# VSCard.net
KiCad netlist of a schematic drawn in EAGLE
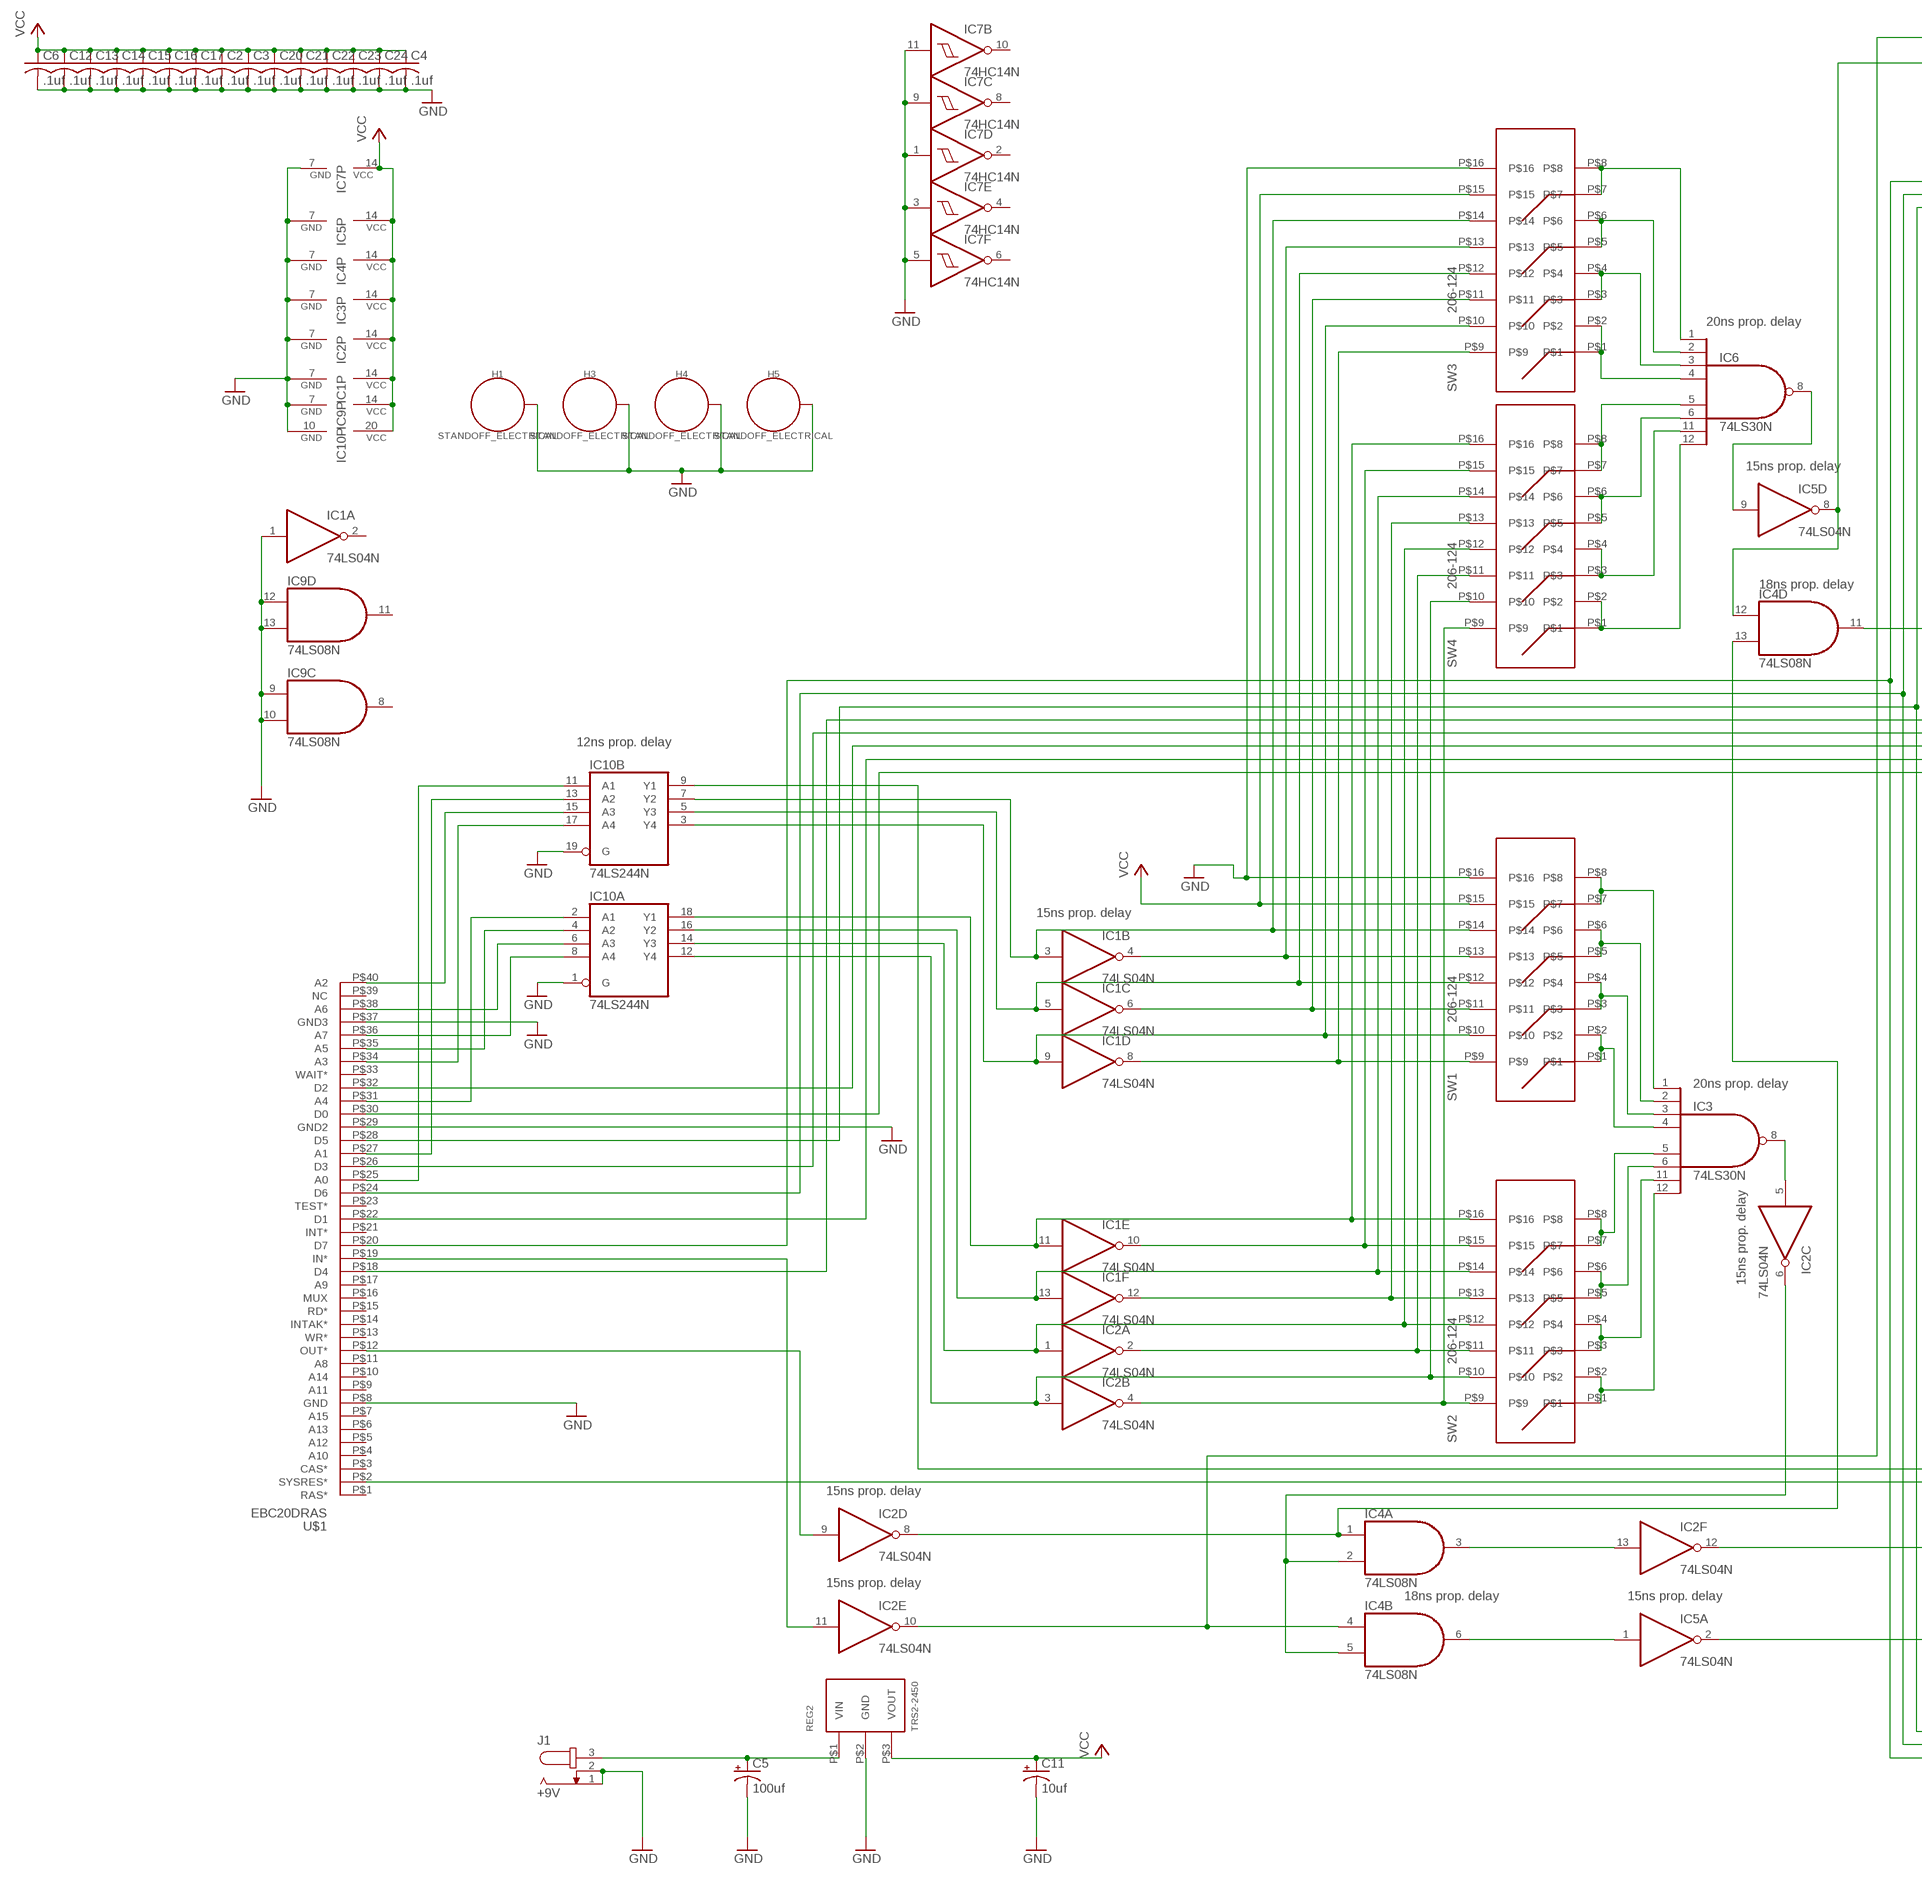
[diagram p0: schematic, sheet 1, part 1 of 3]
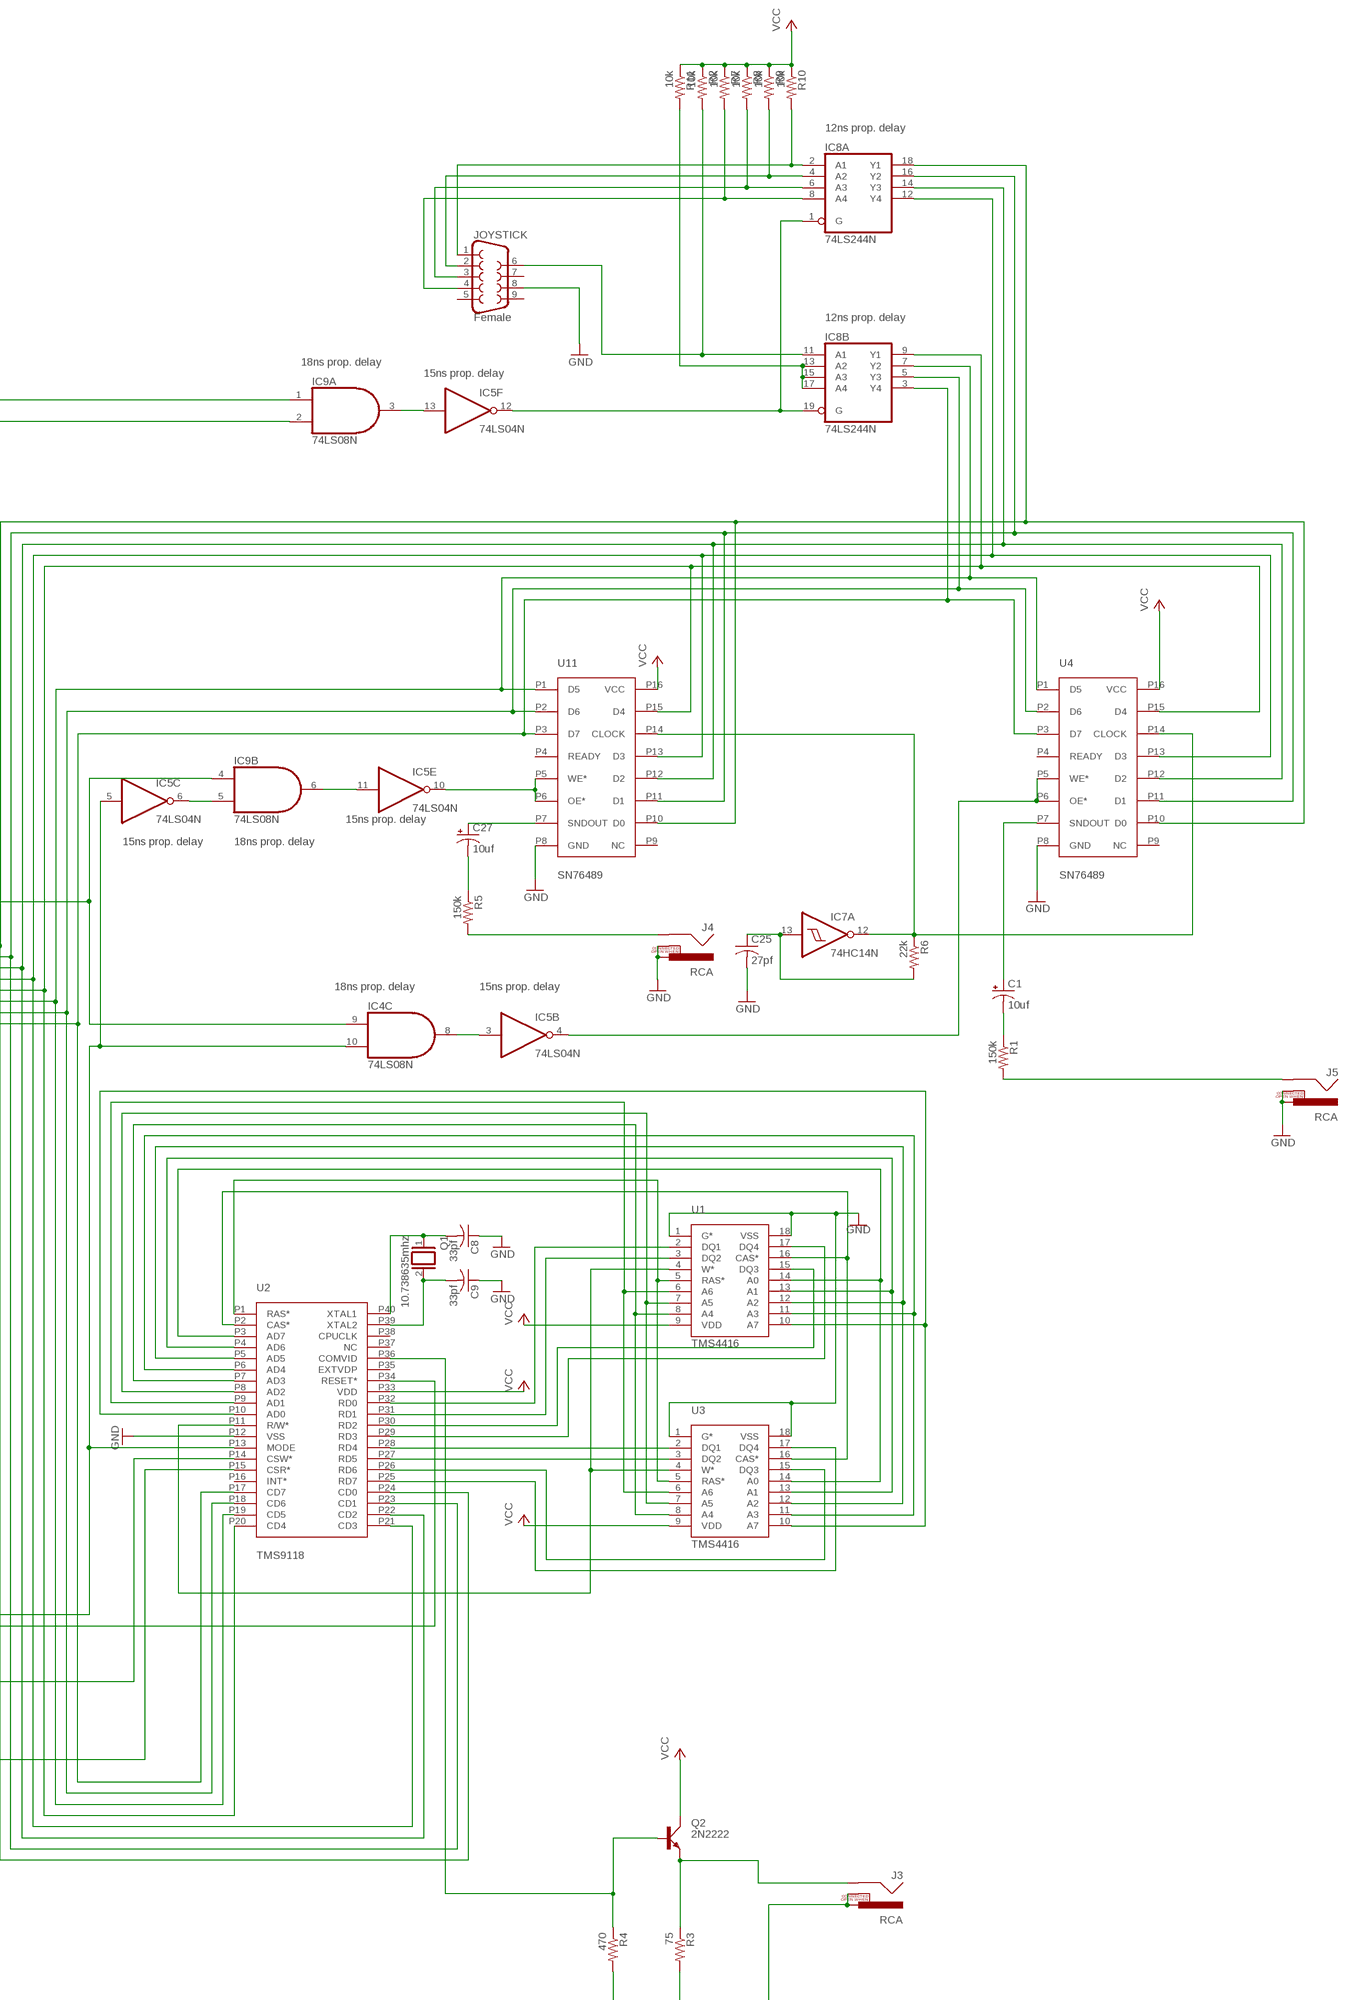
[diagram p1: schematic, sheet 1, part 2 of 3]
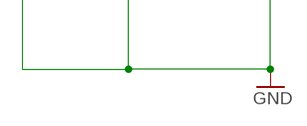
[diagram p2: schematic, sheet 1, part 3 of 3]

(export (version "E")
  (design (tool "Eeschema 10.0.6"))
  (components
    (comp (ref "C1")
      (value "10uf")
      (footprint "eagle-import:E2,5-6")
      (libsource (lib "eagle-import") (part "resistor_348_CPOL-USE2.5-6"))
    )
    (comp (ref "C2")
      (value ".1uf")
      (footprint "eagle-import:C025-025X050")
      (libsource (lib "eagle-import") (part "resistor_348_C-US025-025X050"))
    )
    (comp (ref "C3")
      (value ".1uf")
      (footprint "eagle-import:C025-025X050")
      (libsource (lib "eagle-import") (part "resistor_348_C-US025-025X050"))
    )
    (comp (ref "C4")
      (value ".1uf")
      (footprint "eagle-import:C025-025X050")
      (libsource (lib "eagle-import") (part "resistor_348_C-US025-025X050"))
    )
    (comp (ref "C5")
      (value "100uf")
      (footprint "eagle-import:E3,5-10")
      (libsource (lib "eagle-import") (part "CPOL-USE3.5-10"))
    )
    (comp (ref "C6")
      (value ".1uf")
      (footprint "eagle-import:C025-025X050")
      (libsource (lib "eagle-import") (part "resistor_348_C-US025-025X050"))
    )
    (comp (ref "C8")
      (value "33pf")
      (footprint "eagle-import:C050-050X075")
      (libsource (lib "eagle-import") (part "C-US050-050X075"))
    )
    (comp (ref "C9")
      (value "33pf")
      (footprint "eagle-import:C050-050X075")
      (libsource (lib "eagle-import") (part "C-US050-050X075"))
    )
    (comp (ref "C11")
      (value "10uf")
      (footprint "eagle-import:E3,5-10")
      (libsource (lib "eagle-import") (part "CPOL-USE3.5-10"))
    )
    (comp (ref "C12")
      (value ".1uf")
      (footprint "eagle-import:C025-025X050")
      (libsource (lib "eagle-import") (part "resistor_348_C-US025-025X050"))
    )
    (comp (ref "C13")
      (value ".1uf")
      (footprint "eagle-import:C025-025X050")
      (libsource (lib "eagle-import") (part "resistor_348_C-US025-025X050"))
    )
    (comp (ref "C14")
      (value ".1uf")
      (footprint "eagle-import:C025-025X050")
      (libsource (lib "eagle-import") (part "resistor_348_C-US025-025X050"))
    )
    (comp (ref "C15")
      (value ".1uf")
      (footprint "eagle-import:C025-025X050")
      (libsource (lib "eagle-import") (part "resistor_348_C-US025-025X050"))
    )
    (comp (ref "C16")
      (value ".1uf")
      (footprint "eagle-import:C025-025X050")
      (libsource (lib "eagle-import") (part "resistor_348_C-US025-025X050"))
    )
    (comp (ref "C17")
      (value ".1uf")
      (footprint "eagle-import:C025-025X050")
      (libsource (lib "eagle-import") (part "resistor_348_C-US025-025X050"))
    )
    (comp (ref "C20")
      (value ".1uf")
      (footprint "eagle-import:C025-025X050")
      (libsource (lib "eagle-import") (part "resistor_348_C-US025-025X050"))
    )
    (comp (ref "C21")
      (value ".1uf")
      (footprint "eagle-import:C025-025X050")
      (libsource (lib "eagle-import") (part "resistor_348_C-US025-025X050"))
    )
    (comp (ref "C22")
      (value ".1uf")
      (footprint "eagle-import:C025-025X050")
      (libsource (lib "eagle-import") (part "resistor_348_C-US025-025X050"))
    )
    (comp (ref "C23")
      (value ".1uf")
      (footprint "eagle-import:C025-025X050")
      (libsource (lib "eagle-import") (part "resistor_348_C-US025-025X050"))
    )
    (comp (ref "C24")
      (value ".1uf")
      (footprint "eagle-import:C025-025X050")
      (libsource (lib "eagle-import") (part "resistor_348_C-US025-025X050"))
    )
    (comp (ref "C25")
      (value "27pf")
      (footprint "eagle-import:C025-025X050")
      (libsource (lib "eagle-import") (part "resistor_348_C-US025-025X050"))
    )
    (comp (ref "C27")
      (value "10uf")
      (footprint "eagle-import:E2,5-6")
      (libsource (lib "eagle-import") (part "resistor_348_CPOL-USE2.5-6"))
    )
    (comp (ref "H1")
      (value "STANDOFF_ELECTRICAL")
      (footprint "eagle-import:STANDOFF-ELECTRICAL")
      (libsource (lib "eagle-import") (part "STANDOFF_ELECTRICAL"))
    )
    (comp (ref "H3")
      (value "STANDOFF_ELECTRICAL")
      (footprint "eagle-import:STANDOFF-ELECTRICAL")
      (libsource (lib "eagle-import") (part "STANDOFF_ELECTRICAL"))
    )
    (comp (ref "H4")
      (value "STANDOFF_ELECTRICAL")
      (footprint "eagle-import:STANDOFF-ELECTRICAL")
      (libsource (lib "eagle-import") (part "STANDOFF_ELECTRICAL"))
    )
    (comp (ref "H5")
      (value "STANDOFF_ELECTRICAL")
      (footprint "eagle-import:STANDOFF-ELECTRICAL")
      (libsource (lib "eagle-import") (part "STANDOFF_ELECTRICAL"))
    )
    (comp (ref "IC1")
      (value "74LS04N")
      (footprint "eagle-import:DIL14")
      (libsource (lib "eagle-import") (part "7404NLS"))
    )
    (comp (ref "IC2")
      (value "74LS04N")
      (footprint "eagle-import:DIL14")
      (libsource (lib "eagle-import") (part "7404NLS"))
    )
    (comp (ref "IC3")
      (value "74LS30N")
      (footprint "eagle-import:DIL14")
      (libsource (lib "eagle-import") (part "7430NLS"))
    )
    (comp (ref "IC4")
      (value "74LS08N")
      (footprint "eagle-import:DIL14")
      (libsource (lib "eagle-import") (part "7408NLS"))
    )
    (comp (ref "IC5")
      (value "74LS04N")
      (footprint "eagle-import:DIL14")
      (libsource (lib "eagle-import") (part "7404NLS"))
    )
    (comp (ref "IC6")
      (value "74LS30N")
      (footprint "eagle-import:DIL14")
      (libsource (lib "eagle-import") (part "7430NLS"))
    )
    (comp (ref "IC7")
      (value "74HC14N")
      (footprint "eagle-import:DIL14")
      (libsource (lib "eagle-import") (part "7414NHC"))
    )
    (comp (ref "IC8")
      (value "74LS244N")
      (footprint "eagle-import:DIL20")
      (libsource (lib "eagle-import") (part "74244NLS"))
    )
    (comp (ref "IC9")
      (value "74LS08N")
      (footprint "eagle-import:DIL14")
      (libsource (lib "eagle-import") (part "7408NLS"))
    )
    (comp (ref "IC10")
      (value "74LS244N")
      (footprint "eagle-import:DIL20")
      (libsource (lib "eagle-import") (part "74244NLS"))
    )
    (comp (ref "J1")
      (value "+9V")
      (footprint "eagle-import:SPC4077")
      (libsource (lib "eagle-import") (part "JACK-PLUG0"))
    )
    (comp (ref "J3")
      (value "RCA")
      (footprint "eagle-import:RCA")
      (libsource (lib "eagle-import") (part "RCA"))
    )
    (comp (ref "J4")
      (value "RCA")
      (footprint "eagle-import:RCA")
      (libsource (lib "eagle-import") (part "RCA"))
    )
    (comp (ref "J5")
      (value "RCA")
      (footprint "eagle-import:RCA")
      (libsource (lib "eagle-import") (part "RCA"))
    )
    (comp (ref "JOYSTICK")
      (value "Female")
      (footprint "eagle-import:DB9")
      (libsource (lib "eagle-import") (part "DB9FEMALE"))
    )
    (comp (ref "Q1")
      (value "10.738635mhz")
      (footprint "eagle-import:QS")
      (libsource (lib "eagle-import") (part "XTAL/S"))
    )
    (comp (ref "Q2")
      (value "2N2222")
      (footprint "eagle-import:TO18A")
      (libsource (lib "eagle-import") (part "2N2222"))
    )
    (comp (ref "R1")
      (value "150k")
      (footprint "eagle-import:0207_2V")
      (libsource (lib "eagle-import") (part "R-US_0207/2V"))
    )
    (comp (ref "R2")
      (value "10k")
      (footprint "eagle-import:0207_2V")
      (libsource (lib "eagle-import") (part "R-US_0207/2V"))
    )
    (comp (ref "R3")
      (value "75")
      (footprint "eagle-import:0207_2V")
      (libsource (lib "eagle-import") (part "R-US_0207/2V"))
    )
    (comp (ref "R4")
      (value "470")
      (footprint "eagle-import:0207_2V")
      (libsource (lib "eagle-import") (part "R-US_0207/2V"))
    )
    (comp (ref "R5")
      (value "150k")
      (footprint "eagle-import:0207_2V")
      (libsource (lib "eagle-import") (part "R-US_0207/2V"))
    )
    (comp (ref "R6")
      (value "22k")
      (footprint "eagle-import:0207_2V")
      (libsource (lib "eagle-import") (part "R-US_0207/2V"))
    )
    (comp (ref "R7")
      (value "10k")
      (footprint "eagle-import:0207_2V")
      (libsource (lib "eagle-import") (part "R-US_0207/2V"))
    )
    (comp (ref "R8")
      (value "10k")
      (footprint "eagle-import:0207_2V")
      (libsource (lib "eagle-import") (part "R-US_0207/2V"))
    )
    (comp (ref "R9")
      (value "10k")
      (footprint "eagle-import:0207_2V")
      (libsource (lib "eagle-import") (part "R-US_0207/2V"))
    )
    (comp (ref "R10")
      (value "10k")
      (footprint "eagle-import:0207_2V")
      (libsource (lib "eagle-import") (part "R-US_0207/2V"))
    )
    (comp (ref "R11")
      (value "10k")
      (footprint "eagle-import:0207_2V")
      (libsource (lib "eagle-import") (part "R-US_0207/2V"))
    )
    (comp (ref "REG2")
      (value "TRS2-2450")
      (footprint "eagle-import:TRACON_REG")
      (libsource (lib "eagle-import") (part "TRS2-2450"))
    )
    (comp (ref "SW1")
      (value "206-124")
      (footprint "eagle-import:206-124")
      (libsource (lib "eagle-import") (part "206-124"))
    )
    (comp (ref "SW2")
      (value "206-124")
      (footprint "eagle-import:206-124")
      (libsource (lib "eagle-import") (part "206-124"))
    )
    (comp (ref "SW3")
      (value "206-124")
      (footprint "eagle-import:206-124")
      (libsource (lib "eagle-import") (part "206-124"))
    )
    (comp (ref "SW4")
      (value "206-124")
      (footprint "eagle-import:206-124")
      (libsource (lib "eagle-import") (part "206-124"))
    )
    (comp (ref "U$1")
      (value "EBC20DRAS")
      (footprint "eagle-import:EBC20DRAS")
      (libsource (lib "eagle-import") (part "EBC20DRAS"))
    )
    (comp (ref "U1")
      (value "TMS4416")
      (footprint "eagle-import:DIP18")
      (libsource (lib "eagle-import") (part "TMS4416"))
    )
    (comp (ref "U2")
      (value "TMS9118")
      (footprint "eagle-import:DIP40_MCU")
      (libsource (lib "eagle-import") (part "TMS9118"))
    )
    (comp (ref "U3")
      (value "TMS4416")
      (footprint "eagle-import:DIP18")
      (libsource (lib "eagle-import") (part "TMS4416"))
    )
    (comp (ref "U4")
      (value "SN76489")
      (footprint "eagle-import:DIP16")
      (libsource (lib "eagle-import") (part "SN76489"))
    )
    (comp (ref "U11")
      (value "SN76489")
      (footprint "eagle-import:DIP16")
      (libsource (lib "eagle-import") (part "SN76489"))
    )
  )
  (nets
    (net (code "1") (name "GND") (class "Default")
      (node (ref "C11") (pin "-") (pinfunction "-_-") (pintype "passive"))
      (node (ref "C12") (pin "2") (pinfunction "2_2") (pintype "passive"))
      (node (ref "C13") (pin "2") (pinfunction "2_2") (pintype "passive"))
      (node (ref "C14") (pin "2") (pinfunction "2_2") (pintype "passive"))
      (node (ref "C15") (pin "2") (pinfunction "2_2") (pintype "passive"))
      (node (ref "C16") (pin "2") (pinfunction "2_2") (pintype "passive"))
      (node (ref "C17") (pin "2") (pinfunction "2_2") (pintype "passive"))
      (node (ref "C2") (pin "2") (pinfunction "2_2") (pintype "passive"))
      (node (ref "C20") (pin "2") (pinfunction "2_2") (pintype "passive"))
      (node (ref "C21") (pin "2") (pinfunction "2_2") (pintype "passive"))
      (node (ref "C22") (pin "2") (pinfunction "2_2") (pintype "passive"))
      (node (ref "C23") (pin "2") (pinfunction "2_2") (pintype "passive"))
      (node (ref "C24") (pin "2") (pinfunction "2_2") (pintype "passive"))
      (node (ref "C25") (pin "2") (pinfunction "2_2") (pintype "passive"))
      (node (ref "C3") (pin "2") (pinfunction "2_2") (pintype "passive"))
      (node (ref "C4") (pin "2") (pinfunction "2_2") (pintype "passive"))
      (node (ref "C5") (pin "-") (pinfunction "-_-") (pintype "passive"))
      (node (ref "C6") (pin "2") (pinfunction "2_2") (pintype "passive"))
      (node (ref "C8") (pin "1") (pinfunction "1_1") (pintype "passive"))
      (node (ref "C9") (pin "1") (pinfunction "1_1") (pintype "passive"))
      (node (ref "H1") (pin "P1") (pinfunction "P$1_P1") (pintype "bidirectional"))
      (node (ref "H3") (pin "P1") (pinfunction "P$1_P1") (pintype "bidirectional"))
      (node (ref "H4") (pin "P1") (pinfunction "P$1_P1") (pintype "bidirectional"))
      (node (ref "H5") (pin "P1") (pinfunction "P$1_P1") (pintype "bidirectional"))
      (node (ref "IC1") (pin "1") (pinfunction "I_1") (pintype "input"))
      (node (ref "IC1") (pin "7") (pinfunction "GND_7") (pintype "power_in"))
      (node (ref "IC10") (pin "1") (pinfunction "G_1") (pintype "input"))
      (node (ref "IC10") (pin "10") (pinfunction "GND_10") (pintype "power_in"))
      (node (ref "IC10") (pin "19") (pinfunction "G_19") (pintype "input"))
      (node (ref "IC2") (pin "7") (pinfunction "GND_7") (pintype "power_in"))
      (node (ref "IC3") (pin "7") (pinfunction "GND_7") (pintype "power_in"))
      (node (ref "IC4") (pin "7") (pinfunction "GND_7") (pintype "power_in"))
      (node (ref "IC5") (pin "7") (pinfunction "GND_7") (pintype "power_in"))
      (node (ref "IC7") (pin "1") (pinfunction "I_1") (pintype "input"))
      (node (ref "IC7") (pin "11") (pinfunction "I_11") (pintype "input"))
      (node (ref "IC7") (pin "3") (pinfunction "I_3") (pintype "input"))
      (node (ref "IC7") (pin "5") (pinfunction "I_5") (pintype "input"))
      (node (ref "IC7") (pin "7") (pinfunction "GND_7") (pintype "power_in"))
      (node (ref "IC7") (pin "9") (pinfunction "I_9") (pintype "input"))
      (node (ref "IC9") (pin "10") (pinfunction "I1_10") (pintype "input"))
      (node (ref "IC9") (pin "12") (pinfunction "I0_12") (pintype "input"))
      (node (ref "IC9") (pin "13") (pinfunction "I1_13") (pintype "input"))
      (node (ref "IC9") (pin "7") (pinfunction "GND_7") (pintype "power_in"))
      (node (ref "IC9") (pin "9") (pinfunction "I0_9") (pintype "input"))
      (node (ref "J1") (pin "1") (pinfunction "1_1") (pintype "passive"))
      (node (ref "J1") (pin "2") (pinfunction "2_2") (pintype "passive"))
      (node (ref "J3") (pin "PIN") (pinfunction "PIN_PIN") (pintype "bidirectional"))
      (node (ref "J3") (pin "SWITCH") (pinfunction "SWITCH_SWITCH") (pintype "bidirectional"))
      (node (ref "J4") (pin "PIN") (pinfunction "PIN_PIN") (pintype "bidirectional"))
      (node (ref "J4") (pin "SWITCH") (pinfunction "SWITCH_SWITCH") (pintype "bidirectional"))
      (node (ref "J5") (pin "PIN") (pinfunction "PIN_PIN") (pintype "bidirectional"))
      (node (ref "J5") (pin "SWITCH") (pinfunction "SWITCH_SWITCH") (pintype "bidirectional"))
      (node (ref "JOYSTICK") (pin "8") (pinfunction "8_8") (pintype "passive"))
      (node (ref "R3") (pin "2") (pinfunction "2_2") (pintype "passive"))
      (node (ref "R4") (pin "2") (pinfunction "2_2") (pintype "passive"))
      (node (ref "REG2") (pin "P$2") (pinfunction "GND_P$2") (pintype "bidirectional"))
      (node (ref "SW1") (pin "P$16") (pinfunction "P$16_P$16") (pintype "bidirectional"))
      (node (ref "SW3") (pin "P$16") (pinfunction "P$16_P$16") (pintype "bidirectional"))
      (node (ref "U$1") (pin "P$29") (pinfunction "GND2_P$29") (pintype "bidirectional"))
      (node (ref "U$1") (pin "P$37") (pinfunction "GND3_P$37") (pintype "bidirectional"))
      (node (ref "U$1") (pin "P$8") (pinfunction "GND_P$8") (pintype "bidirectional"))
      (node (ref "U1") (pin "1") (pinfunction "G*_1") (pintype "bidirectional"))
      (node (ref "U1") (pin "18") (pinfunction "VSS_18") (pintype "bidirectional"))
      (node (ref "U11") (pin "P8") (pinfunction "GND_P8") (pintype "bidirectional"))
      (node (ref "U2") (pin "P12") (pinfunction "VSS_P12") (pintype "bidirectional"))
      (node (ref "U3") (pin "1") (pinfunction "G*_1") (pintype "bidirectional"))
      (node (ref "U3") (pin "18") (pinfunction "VSS_18") (pintype "bidirectional"))
      (node (ref "U4") (pin "P8") (pinfunction "GND_P8") (pintype "bidirectional"))
    )
    (net (code "2") (name "Net-(C1-Pad-)") (class "Default")
      (node (ref "C1") (pin "-") (pinfunction "-_-") (pintype "passive"))
      (node (ref "R1") (pin "1") (pinfunction "1_1") (pintype "passive"))
    )
    (net (code "3") (name "Net-(C27-Pad-)") (class "Default")
      (node (ref "C27") (pin "-") (pinfunction "-_-") (pintype "passive"))
      (node (ref "R5") (pin "1") (pinfunction "1_1") (pintype "passive"))
    )
    (net (code "4") (name "Net-(IC1B-O)") (class "Default")
      (node (ref "IC1") (pin "4") (pinfunction "O_4") (pintype "output"))
      (node (ref "SW1") (pin "P$13") (pinfunction "P$13_P$13") (pintype "bidirectional"))
      (node (ref "SW3") (pin "P$13") (pinfunction "P$13_P$13") (pintype "bidirectional"))
    )
    (net (code "5") (name "Net-(IC1C-O)") (class "Default")
      (node (ref "IC1") (pin "6") (pinfunction "O_6") (pintype "output"))
      (node (ref "SW1") (pin "P$11") (pinfunction "P$11_P$11") (pintype "bidirectional"))
      (node (ref "SW3") (pin "P$11") (pinfunction "P$11_P$11") (pintype "bidirectional"))
    )
    (net (code "6") (name "Net-(IC1D-O)") (class "Default")
      (node (ref "IC1") (pin "8") (pinfunction "O_8") (pintype "output"))
      (node (ref "SW1") (pin "P$9") (pinfunction "P$9_P$9") (pintype "bidirectional"))
      (node (ref "SW3") (pin "P$9") (pinfunction "P$9_P$9") (pintype "bidirectional"))
    )
    (net (code "7") (name "Net-(IC1E-O)") (class "Default")
      (node (ref "IC1") (pin "10") (pinfunction "O_10") (pintype "output"))
      (node (ref "SW2") (pin "P$15") (pinfunction "P$15_P$15") (pintype "bidirectional"))
      (node (ref "SW4") (pin "P$15") (pinfunction "P$15_P$15") (pintype "bidirectional"))
    )
    (net (code "8") (name "Net-(IC1F-O)") (class "Default")
      (node (ref "IC1") (pin "12") (pinfunction "O_12") (pintype "output"))
      (node (ref "SW2") (pin "P$13") (pinfunction "P$13_P$13") (pintype "bidirectional"))
      (node (ref "SW4") (pin "P$13") (pinfunction "P$13_P$13") (pintype "bidirectional"))
    )
    (net (code "9") (name "Net-(IC2A-O)") (class "Default")
      (node (ref "IC2") (pin "2") (pinfunction "O_2") (pintype "output"))
      (node (ref "SW2") (pin "P$11") (pinfunction "P$11_P$11") (pintype "bidirectional"))
      (node (ref "SW4") (pin "P$11") (pinfunction "P$11_P$11") (pintype "bidirectional"))
    )
    (net (code "10") (name "Net-(IC2B-O)") (class "Default")
      (node (ref "IC2") (pin "4") (pinfunction "O_4") (pintype "output"))
      (node (ref "SW2") (pin "P$9") (pinfunction "P$9_P$9") (pintype "bidirectional"))
      (node (ref "SW4") (pin "P$9") (pinfunction "P$9_P$9") (pintype "bidirectional"))
    )
    (net (code "11") (name "Net-(IC2C-I)") (class "Default")
      (node (ref "IC2") (pin "5") (pinfunction "I_5") (pintype "input"))
      (node (ref "IC3") (pin "8") (pinfunction "O_8") (pintype "output"))
    )
    (net (code "12") (name "Net-(IC2C-O)") (class "Default")
      (node (ref "IC2") (pin "6") (pinfunction "O_6") (pintype "output"))
      (node (ref "IC4") (pin "2") (pinfunction "I1_2") (pintype "input"))
      (node (ref "IC4") (pin "5") (pinfunction "I1_5") (pintype "input"))
    )
    (net (code "13") (name "Net-(IC2D-I)") (class "Default")
      (node (ref "IC2") (pin "9") (pinfunction "I_9") (pintype "input"))
      (node (ref "U$1") (pin "P$12") (pinfunction "OUT*_P$12") (pintype "bidirectional"))
    )
    (net (code "14") (name "Net-(IC2D-O)") (class "Default")
      (node (ref "IC2") (pin "8") (pinfunction "O_8") (pintype "output"))
      (node (ref "IC4") (pin "1") (pinfunction "I0_1") (pintype "input"))
      (node (ref "IC4") (pin "13") (pinfunction "I1_13") (pintype "input"))
    )
    (net (code "15") (name "Net-(IC2E-I)") (class "Default")
      (node (ref "IC2") (pin "11") (pinfunction "I_11") (pintype "input"))
      (node (ref "U$1") (pin "P$19") (pinfunction "IN*_P$19") (pintype "bidirectional"))
    )
    (net (code "16") (name "Net-(IC2E-O)") (class "Default")
      (node (ref "IC2") (pin "10") (pinfunction "O_10") (pintype "output"))
      (node (ref "IC4") (pin "4") (pinfunction "I0_4") (pintype "input"))
      (node (ref "IC9") (pin "1") (pinfunction "I0_1") (pintype "input"))
    )
    (net (code "17") (name "Net-(IC2F-I)") (class "Default")
      (node (ref "IC2") (pin "13") (pinfunction "I_13") (pintype "input"))
      (node (ref "IC4") (pin "3") (pinfunction "O_3") (pintype "output"))
    )
    (net (code "18") (name "Net-(IC2F-O)") (class "Default")
      (node (ref "IC2") (pin "12") (pinfunction "O_12") (pintype "output"))
      (node (ref "U2") (pin "P14") (pinfunction "CSW*_P14") (pintype "bidirectional"))
    )
    (net (code "19") (name "Net-(IC3A-I0)") (class "Default")
      (node (ref "IC3") (pin "1") (pinfunction "I0_1") (pintype "input"))
      (node (ref "SW1") (pin "P$7") (pinfunction "P$7_P$7") (pintype "bidirectional"))
      (node (ref "SW1") (pin "P$8") (pinfunction "P$8_P$8") (pintype "bidirectional"))
    )
    (net (code "20") (name "Net-(IC3A-I1)") (class "Default")
      (node (ref "IC3") (pin "2") (pinfunction "I1_2") (pintype "input"))
      (node (ref "SW1") (pin "P$5") (pinfunction "P$5_P$5") (pintype "bidirectional"))
      (node (ref "SW1") (pin "P$6") (pinfunction "P$6_P$6") (pintype "bidirectional"))
    )
    (net (code "21") (name "Net-(IC3A-I2)") (class "Default")
      (node (ref "IC3") (pin "3") (pinfunction "I2_3") (pintype "input"))
      (node (ref "SW1") (pin "P$3") (pinfunction "P$3_P$3") (pintype "bidirectional"))
      (node (ref "SW1") (pin "P$4") (pinfunction "P$4_P$4") (pintype "bidirectional"))
    )
    (net (code "22") (name "Net-(IC3A-I3)") (class "Default")
      (node (ref "IC3") (pin "4") (pinfunction "I3_4") (pintype "input"))
      (node (ref "SW1") (pin "P$1") (pinfunction "P$1_P$1") (pintype "bidirectional"))
      (node (ref "SW1") (pin "P$2") (pinfunction "P$2_P$2") (pintype "bidirectional"))
    )
    (net (code "23") (name "Net-(IC3A-I4)") (class "Default")
      (node (ref "IC3") (pin "5") (pinfunction "I4_5") (pintype "input"))
      (node (ref "SW2") (pin "P$7") (pinfunction "P$7_P$7") (pintype "bidirectional"))
      (node (ref "SW2") (pin "P$8") (pinfunction "P$8_P$8") (pintype "bidirectional"))
    )
    (net (code "24") (name "Net-(IC3A-I5)") (class "Default")
      (node (ref "IC3") (pin "6") (pinfunction "I5_6") (pintype "input"))
      (node (ref "SW2") (pin "P$5") (pinfunction "P$5_P$5") (pintype "bidirectional"))
      (node (ref "SW2") (pin "P$6") (pinfunction "P$6_P$6") (pintype "bidirectional"))
    )
    (net (code "25") (name "Net-(IC3A-I6)") (class "Default")
      (node (ref "IC3") (pin "11") (pinfunction "I6_11") (pintype "input"))
      (node (ref "SW2") (pin "P$3") (pinfunction "P$3_P$3") (pintype "bidirectional"))
      (node (ref "SW2") (pin "P$4") (pinfunction "P$4_P$4") (pintype "bidirectional"))
    )
    (net (code "26") (name "Net-(IC3A-I7)") (class "Default")
      (node (ref "IC3") (pin "12") (pinfunction "I7_12") (pintype "input"))
      (node (ref "SW2") (pin "P$1") (pinfunction "P$1_P$1") (pintype "bidirectional"))
      (node (ref "SW2") (pin "P$2") (pinfunction "P$2_P$2") (pintype "bidirectional"))
    )
    (net (code "27") (name "Net-(IC4B-O)") (class "Default")
      (node (ref "IC4") (pin "6") (pinfunction "O_6") (pintype "output"))
      (node (ref "IC5") (pin "1") (pinfunction "I_1") (pintype "input"))
    )
    (net (code "28") (name "Net-(IC4C-I0)") (class "Default")
      (node (ref "IC4") (pin "11") (pinfunction "O_11") (pintype "output"))
      (node (ref "IC4") (pin "9") (pinfunction "I0_9") (pintype "input"))
      (node (ref "IC9") (pin "4") (pinfunction "I0_4") (pintype "input"))
    )
    (net (code "29") (name "Net-(IC4C-O)") (class "Default")
      (node (ref "IC4") (pin "8") (pinfunction "O_8") (pintype "output"))
      (node (ref "IC5") (pin "3") (pinfunction "I_3") (pintype "input"))
    )
    (net (code "30") (name "Net-(IC4D-I0)") (class "Default")
      (node (ref "IC4") (pin "12") (pinfunction "I0_12") (pintype "input"))
      (node (ref "IC5") (pin "8") (pinfunction "O_8") (pintype "output"))
      (node (ref "IC9") (pin "2") (pinfunction "I1_2") (pintype "input"))
    )
    (net (code "31") (name "Net-(IC5A-O)") (class "Default")
      (node (ref "IC5") (pin "2") (pinfunction "O_2") (pintype "output"))
      (node (ref "U2") (pin "P15") (pinfunction "CSR*_P15") (pintype "bidirectional"))
    )
    (net (code "32") (name "Net-(IC5B-O)") (class "Default")
      (node (ref "IC5") (pin "4") (pinfunction "O_4") (pintype "output"))
      (node (ref "U4") (pin "P5") (pinfunction "WE*_P5") (pintype "bidirectional"))
      (node (ref "U4") (pin "P6") (pinfunction "OE*_P6") (pintype "bidirectional"))
    )
    (net (code "33") (name "Net-(IC5C-O)") (class "Default")
      (node (ref "IC5") (pin "6") (pinfunction "O_6") (pintype "output"))
      (node (ref "IC9") (pin "5") (pinfunction "I1_5") (pintype "input"))
    )
    (net (code "34") (name "Net-(IC5D-I)") (class "Default")
      (node (ref "IC5") (pin "9") (pinfunction "I_9") (pintype "input"))
      (node (ref "IC6") (pin "8") (pinfunction "O_8") (pintype "output"))
    )
    (net (code "35") (name "Net-(IC5E-I)") (class "Default")
      (node (ref "IC5") (pin "11") (pinfunction "I_11") (pintype "input"))
      (node (ref "IC9") (pin "6") (pinfunction "O_6") (pintype "output"))
    )
    (net (code "36") (name "Net-(IC5E-O)") (class "Default")
      (node (ref "IC5") (pin "10") (pinfunction "O_10") (pintype "output"))
      (node (ref "U11") (pin "P5") (pinfunction "WE*_P5") (pintype "bidirectional"))
      (node (ref "U11") (pin "P6") (pinfunction "OE*_P6") (pintype "bidirectional"))
    )
    (net (code "37") (name "Net-(IC5F-I)") (class "Default")
      (node (ref "IC5") (pin "13") (pinfunction "I_13") (pintype "input"))
      (node (ref "IC9") (pin "3") (pinfunction "O_3") (pintype "output"))
    )
    (net (code "38") (name "Net-(IC5F-O)") (class "Default")
      (node (ref "IC5") (pin "12") (pinfunction "O_12") (pintype "output"))
      (node (ref "IC8") (pin "1") (pinfunction "G_1") (pintype "input"))
      (node (ref "IC8") (pin "19") (pinfunction "G_19") (pintype "input"))
    )
    (net (code "39") (name "Net-(IC6A-I0)") (class "Default")
      (node (ref "IC6") (pin "1") (pinfunction "I0_1") (pintype "input"))
      (node (ref "SW3") (pin "P$7") (pinfunction "P$7_P$7") (pintype "bidirectional"))
      (node (ref "SW3") (pin "P$8") (pinfunction "P$8_P$8") (pintype "bidirectional"))
    )
    (net (code "40") (name "Net-(IC6A-I1)") (class "Default")
      (node (ref "IC6") (pin "2") (pinfunction "I1_2") (pintype "input"))
      (node (ref "SW3") (pin "P$5") (pinfunction "P$5_P$5") (pintype "bidirectional"))
      (node (ref "SW3") (pin "P$6") (pinfunction "P$6_P$6") (pintype "bidirectional"))
    )
    (net (code "41") (name "Net-(IC6A-I2)") (class "Default")
      (node (ref "IC6") (pin "3") (pinfunction "I2_3") (pintype "input"))
      (node (ref "SW3") (pin "P$3") (pinfunction "P$3_P$3") (pintype "bidirectional"))
      (node (ref "SW3") (pin "P$4") (pinfunction "P$4_P$4") (pintype "bidirectional"))
    )
    (net (code "42") (name "Net-(IC6A-I3)") (class "Default")
      (node (ref "IC6") (pin "4") (pinfunction "I3_4") (pintype "input"))
      (node (ref "SW3") (pin "P$1") (pinfunction "P$1_P$1") (pintype "bidirectional"))
      (node (ref "SW3") (pin "P$2") (pinfunction "P$2_P$2") (pintype "bidirectional"))
    )
    (net (code "43") (name "Net-(IC6A-I4)") (class "Default")
      (node (ref "IC6") (pin "5") (pinfunction "I4_5") (pintype "input"))
      (node (ref "SW4") (pin "P$7") (pinfunction "P$7_P$7") (pintype "bidirectional"))
      (node (ref "SW4") (pin "P$8") (pinfunction "P$8_P$8") (pintype "bidirectional"))
    )
    (net (code "44") (name "Net-(IC6A-I5)") (class "Default")
      (node (ref "IC6") (pin "6") (pinfunction "I5_6") (pintype "input"))
      (node (ref "SW4") (pin "P$5") (pinfunction "P$5_P$5") (pintype "bidirectional"))
      (node (ref "SW4") (pin "P$6") (pinfunction "P$6_P$6") (pintype "bidirectional"))
    )
    (net (code "45") (name "Net-(IC6A-I6)") (class "Default")
      (node (ref "IC6") (pin "11") (pinfunction "I6_11") (pintype "input"))
      (node (ref "SW4") (pin "P$3") (pinfunction "P$3_P$3") (pintype "bidirectional"))
      (node (ref "SW4") (pin "P$4") (pinfunction "P$4_P$4") (pintype "bidirectional"))
    )
    (net (code "46") (name "Net-(IC6A-I7)") (class "Default")
      (node (ref "IC6") (pin "12") (pinfunction "I7_12") (pintype "input"))
      (node (ref "SW4") (pin "P$1") (pinfunction "P$1_P$1") (pintype "bidirectional"))
      (node (ref "SW4") (pin "P$2") (pinfunction "P$2_P$2") (pintype "bidirectional"))
    )
    (net (code "47") (name "Net-(IC7A-I)") (class "Default")
      (node (ref "C25") (pin "1") (pinfunction "1_1") (pintype "passive"))
      (node (ref "IC7") (pin "13") (pinfunction "I_13") (pintype "input"))
      (node (ref "R6") (pin "2") (pinfunction "2_2") (pintype "passive"))
    )
    (net (code "48") (name "Net-(IC7A-O)") (class "Default")
      (node (ref "IC7") (pin "12") (pinfunction "O_12") (pintype "output"))
      (node (ref "R6") (pin "1") (pinfunction "1_1") (pintype "passive"))
      (node (ref "U11") (pin "P14") (pinfunction "CLOCK_P14") (pintype "bidirectional"))
      (node (ref "U4") (pin "P14") (pinfunction "CLOCK_P14") (pintype "bidirectional"))
    )
    (net (code "49") (name "Net-(IC8A-A1)") (class "Default")
      (node (ref "IC8") (pin "2") (pinfunction "A1_2") (pintype "input"))
      (node (ref "JOYSTICK") (pin "1") (pinfunction "1_1") (pintype "passive"))
      (node (ref "R10") (pin "2") (pinfunction "2_2") (pintype "passive"))
    )
    (net (code "50") (name "Net-(IC8A-A2)") (class "Default")
      (node (ref "IC8") (pin "4") (pinfunction "A2_4") (pintype "input"))
      (node (ref "JOYSTICK") (pin "2") (pinfunction "2_2") (pintype "passive"))
      (node (ref "R9") (pin "2") (pinfunction "2_2") (pintype "passive"))
    )
    (net (code "51") (name "Net-(IC8A-A3)") (class "Default")
      (node (ref "IC8") (pin "6") (pinfunction "A3_6") (pintype "input"))
      (node (ref "JOYSTICK") (pin "3") (pinfunction "3_3") (pintype "passive"))
      (node (ref "R8") (pin "2") (pinfunction "2_2") (pintype "passive"))
    )
    (net (code "52") (name "Net-(IC8A-A4)") (class "Default")
      (node (ref "IC8") (pin "8") (pinfunction "A4_8") (pintype "input"))
      (node (ref "JOYSTICK") (pin "4") (pinfunction "4_4") (pintype "passive"))
      (node (ref "R7") (pin "2") (pinfunction "2_2") (pintype "passive"))
    )
    (net (code "53") (name "Net-(IC8A-Y1)") (class "Default")
      (node (ref "IC8") (pin "18") (pinfunction "Y1_18") (pintype "tri_state"))
      (node (ref "U$1") (pin "P$20") (pinfunction "D7_P$20") (pintype "bidirectional"))
      (node (ref "U11") (pin "P10") (pinfunction "D0_P10") (pintype "bidirectional"))
      (node (ref "U2") (pin "P24") (pinfunction "CD0_P24") (pintype "bidirectional"))
      (node (ref "U4") (pin "P10") (pinfunction "D0_P10") (pintype "bidirectional"))
    )
    (net (code "54") (name "Net-(IC8A-Y2)") (class "Default")
      (node (ref "IC8") (pin "16") (pinfunction "Y2_16") (pintype "tri_state"))
      (node (ref "U$1") (pin "P$24") (pinfunction "D6_P$24") (pintype "bidirectional"))
      (node (ref "U11") (pin "P11") (pinfunction "D1_P11") (pintype "bidirectional"))
      (node (ref "U2") (pin "P23") (pinfunction "CD1_P23") (pintype "bidirectional"))
      (node (ref "U4") (pin "P11") (pinfunction "D1_P11") (pintype "bidirectional"))
    )
    (net (code "55") (name "Net-(IC8A-Y3)") (class "Default")
      (node (ref "IC8") (pin "14") (pinfunction "Y3_14") (pintype "tri_state"))
      (node (ref "U$1") (pin "P$28") (pinfunction "D5_P$28") (pintype "bidirectional"))
      (node (ref "U11") (pin "P12") (pinfunction "D2_P12") (pintype "bidirectional"))
      (node (ref "U2") (pin "P22") (pinfunction "CD2_P22") (pintype "bidirectional"))
      (node (ref "U4") (pin "P12") (pinfunction "D2_P12") (pintype "bidirectional"))
    )
    (net (code "56") (name "Net-(IC8A-Y4)") (class "Default")
      (node (ref "IC8") (pin "12") (pinfunction "Y4_12") (pintype "tri_state"))
      (node (ref "U$1") (pin "P$18") (pinfunction "D4_P$18") (pintype "bidirectional"))
      (node (ref "U11") (pin "P13") (pinfunction "D3_P13") (pintype "bidirectional"))
      (node (ref "U2") (pin "P21") (pinfunction "CD3_P21") (pintype "bidirectional"))
      (node (ref "U4") (pin "P13") (pinfunction "D3_P13") (pintype "bidirectional"))
    )
    (net (code "57") (name "Net-(IC8B-A1)") (class "Default")
      (node (ref "IC8") (pin "11") (pinfunction "A1_11") (pintype "input"))
      (node (ref "JOYSTICK") (pin "6") (pinfunction "6_6") (pintype "passive"))
      (node (ref "R2") (pin "2") (pinfunction "2_2") (pintype "passive"))
    )
    (net (code "58") (name "Net-(IC8B-A2)") (class "Default")
      (node (ref "IC8") (pin "13") (pinfunction "A2_13") (pintype "input"))
      (node (ref "IC8") (pin "15") (pinfunction "A3_15") (pintype "input"))
      (node (ref "IC8") (pin "17") (pinfunction "A4_17") (pintype "input"))
      (node (ref "R11") (pin "2") (pinfunction "2_2") (pintype "passive"))
    )
    (net (code "59") (name "Net-(IC8B-Y1)") (class "Default")
      (node (ref "IC8") (pin "9") (pinfunction "Y1_9") (pintype "tri_state"))
      (node (ref "U$1") (pin "P$26") (pinfunction "D3_P$26") (pintype "bidirectional"))
      (node (ref "U11") (pin "P15") (pinfunction "D4_P15") (pintype "bidirectional"))
      (node (ref "U2") (pin "P20") (pinfunction "CD4_P20") (pintype "bidirectional"))
      (node (ref "U4") (pin "P15") (pinfunction "D4_P15") (pintype "bidirectional"))
    )
    (net (code "60") (name "Net-(IC8B-Y2)") (class "Default")
      (node (ref "IC8") (pin "7") (pinfunction "Y2_7") (pintype "tri_state"))
      (node (ref "U$1") (pin "P$32") (pinfunction "D2_P$32") (pintype "bidirectional"))
      (node (ref "U11") (pin "P1") (pinfunction "D5_P1") (pintype "bidirectional"))
      (node (ref "U2") (pin "P19") (pinfunction "CD5_P19") (pintype "bidirectional"))
      (node (ref "U4") (pin "P1") (pinfunction "D5_P1") (pintype "bidirectional"))
    )
    (net (code "61") (name "Net-(IC8B-Y3)") (class "Default")
      (node (ref "IC8") (pin "5") (pinfunction "Y3_5") (pintype "tri_state"))
      (node (ref "U$1") (pin "P$22") (pinfunction "D1_P$22") (pintype "bidirectional"))
      (node (ref "U11") (pin "P2") (pinfunction "D6_P2") (pintype "bidirectional"))
      (node (ref "U2") (pin "P18") (pinfunction "CD6_P18") (pintype "bidirectional"))
      (node (ref "U4") (pin "P2") (pinfunction "D6_P2") (pintype "bidirectional"))
    )
    (net (code "62") (name "Net-(IC8B-Y4)") (class "Default")
      (node (ref "IC8") (pin "3") (pinfunction "Y4_3") (pintype "tri_state"))
      (node (ref "U$1") (pin "P$30") (pinfunction "D0_P$30") (pintype "bidirectional"))
      (node (ref "U11") (pin "P3") (pinfunction "D7_P3") (pintype "bidirectional"))
      (node (ref "U2") (pin "P17") (pinfunction "CD7_P17") (pintype "bidirectional"))
      (node (ref "U4") (pin "P3") (pinfunction "D7_P3") (pintype "bidirectional"))
    )
    (net (code "63") (name "Net-(IC10A-A1)") (class "Default")
      (node (ref "IC10") (pin "2") (pinfunction "A1_2") (pintype "input"))
      (node (ref "U$1") (pin "P$31") (pinfunction "A4_P$31") (pintype "bidirectional"))
    )
    (net (code "64") (name "Net-(IC10A-A2)") (class "Default")
      (node (ref "IC10") (pin "4") (pinfunction "A2_4") (pintype "input"))
      (node (ref "U$1") (pin "P$35") (pinfunction "A5_P$35") (pintype "bidirectional"))
    )
    (net (code "65") (name "Net-(IC10A-A3)") (class "Default")
      (node (ref "IC10") (pin "6") (pinfunction "A3_6") (pintype "input"))
      (node (ref "U$1") (pin "P$38") (pinfunction "A6_P$38") (pintype "bidirectional"))
    )
    (net (code "66") (name "Net-(IC10A-A4)") (class "Default")
      (node (ref "IC10") (pin "8") (pinfunction "A4_8") (pintype "input"))
      (node (ref "U$1") (pin "P$36") (pinfunction "A7_P$36") (pintype "bidirectional"))
    )
    (net (code "67") (name "Net-(IC10A-Y1)") (class "Default")
      (node (ref "IC1") (pin "11") (pinfunction "I_11") (pintype "input"))
      (node (ref "IC10") (pin "18") (pinfunction "Y1_18") (pintype "tri_state"))
      (node (ref "SW2") (pin "P$16") (pinfunction "P$16_P$16") (pintype "bidirectional"))
      (node (ref "SW4") (pin "P$16") (pinfunction "P$16_P$16") (pintype "bidirectional"))
    )
    (net (code "68") (name "Net-(IC10A-Y2)") (class "Default")
      (node (ref "IC1") (pin "13") (pinfunction "I_13") (pintype "input"))
      (node (ref "IC10") (pin "16") (pinfunction "Y2_16") (pintype "tri_state"))
      (node (ref "SW2") (pin "P$14") (pinfunction "P$14_P$14") (pintype "bidirectional"))
      (node (ref "SW4") (pin "P$14") (pinfunction "P$14_P$14") (pintype "bidirectional"))
    )
    (net (code "69") (name "Net-(IC10A-Y3)") (class "Default")
      (node (ref "IC10") (pin "14") (pinfunction "Y3_14") (pintype "tri_state"))
      (node (ref "IC2") (pin "1") (pinfunction "I_1") (pintype "input"))
      (node (ref "SW2") (pin "P$12") (pinfunction "P$12_P$12") (pintype "bidirectional"))
      (node (ref "SW4") (pin "P$12") (pinfunction "P$12_P$12") (pintype "bidirectional"))
    )
    (net (code "70") (name "Net-(IC10A-Y4)") (class "Default")
      (node (ref "IC10") (pin "12") (pinfunction "Y4_12") (pintype "tri_state"))
      (node (ref "IC2") (pin "3") (pinfunction "I_3") (pintype "input"))
      (node (ref "SW2") (pin "P$10") (pinfunction "P$10_P$10") (pintype "bidirectional"))
      (node (ref "SW4") (pin "P$10") (pinfunction "P$10_P$10") (pintype "bidirectional"))
    )
    (net (code "71") (name "Net-(IC10B-A1)") (class "Default")
      (node (ref "IC10") (pin "11") (pinfunction "A1_11") (pintype "input"))
      (node (ref "U$1") (pin "P$25") (pinfunction "A0_P$25") (pintype "bidirectional"))
    )
    (net (code "72") (name "Net-(IC10B-A2)") (class "Default")
      (node (ref "IC10") (pin "13") (pinfunction "A2_13") (pintype "input"))
      (node (ref "U$1") (pin "P$27") (pinfunction "A1_P$27") (pintype "bidirectional"))
    )
    (net (code "73") (name "Net-(IC10B-A3)") (class "Default")
      (node (ref "IC10") (pin "15") (pinfunction "A3_15") (pintype "input"))
      (node (ref "U$1") (pin "P$40") (pinfunction "A2_P$40") (pintype "bidirectional"))
    )
    (net (code "74") (name "Net-(IC10B-A4)") (class "Default")
      (node (ref "IC10") (pin "17") (pinfunction "A4_17") (pintype "input"))
      (node (ref "U$1") (pin "P$34") (pinfunction "A3_P$34") (pintype "bidirectional"))
    )
    (net (code "75") (name "Net-(IC10B-Y1)") (class "Default")
      (node (ref "IC10") (pin "9") (pinfunction "Y1_9") (pintype "tri_state"))
      (node (ref "IC4") (pin "10") (pinfunction "I1_10") (pintype "input"))
      (node (ref "IC5") (pin "5") (pinfunction "I_5") (pintype "input"))
      (node (ref "U2") (pin "P13") (pinfunction "MODE_P13") (pintype "bidirectional"))
    )
    (net (code "76") (name "Net-(IC10B-Y2)") (class "Default")
      (node (ref "IC1") (pin "3") (pinfunction "I_3") (pintype "input"))
      (node (ref "IC10") (pin "7") (pinfunction "Y2_7") (pintype "tri_state"))
      (node (ref "SW1") (pin "P$14") (pinfunction "P$14_P$14") (pintype "bidirectional"))
      (node (ref "SW3") (pin "P$14") (pinfunction "P$14_P$14") (pintype "bidirectional"))
    )
    (net (code "77") (name "Net-(IC10B-Y3)") (class "Default")
      (node (ref "IC1") (pin "5") (pinfunction "I_5") (pintype "input"))
      (node (ref "IC10") (pin "5") (pinfunction "Y3_5") (pintype "tri_state"))
      (node (ref "SW1") (pin "P$12") (pinfunction "P$12_P$12") (pintype "bidirectional"))
      (node (ref "SW3") (pin "P$12") (pinfunction "P$12_P$12") (pintype "bidirectional"))
    )
    (net (code "78") (name "Net-(IC10B-Y4)") (class "Default")
      (node (ref "IC1") (pin "9") (pinfunction "I_9") (pintype "input"))
      (node (ref "IC10") (pin "3") (pinfunction "Y4_3") (pintype "tri_state"))
      (node (ref "SW1") (pin "P$10") (pinfunction "P$10_P$10") (pintype "bidirectional"))
      (node (ref "SW3") (pin "P$10") (pinfunction "P$10_P$10") (pintype "bidirectional"))
    )
    (net (code "79") (name "Net-(J3-PadSHELL)") (class "Default")
      (node (ref "J3") (pin "SHELL") (pinfunction "SHELL_SHELL") (pintype "bidirectional"))
      (node (ref "Q2") (pin "E") (pinfunction "E_E") (pintype "passive"))
      (node (ref "R3") (pin "1") (pinfunction "1_1") (pintype "passive"))
    )
    (net (code "80") (name "Net-(J4-PadSHELL)") (class "Default")
      (node (ref "J4") (pin "SHELL") (pinfunction "SHELL_SHELL") (pintype "bidirectional"))
      (node (ref "R5") (pin "2") (pinfunction "2_2") (pintype "passive"))
    )
    (net (code "81") (name "Net-(J5-PadSHELL)") (class "Default")
      (node (ref "J5") (pin "SHELL") (pinfunction "SHELL_SHELL") (pintype "bidirectional"))
      (node (ref "R1") (pin "2") (pinfunction "2_2") (pintype "passive"))
    )
    (net (code "82") (name "Net-(REG2-VIN)") (class "Default")
      (node (ref "C5") (pin "+") (pinfunction "+_+") (pintype "passive"))
      (node (ref "J1") (pin "3") (pinfunction "3_3") (pintype "passive"))
      (node (ref "REG2") (pin "P$1") (pinfunction "VIN_P$1") (pintype "bidirectional"))
    )
    (net (code "83") (name "Net-(U$1-SYSRES*)") (class "Default")
      (node (ref "U$1") (pin "P$2") (pinfunction "SYSRES*_P$2") (pintype "bidirectional"))
      (node (ref "U2") (pin "P34") (pinfunction "RESET*_P34") (pintype "bidirectional"))
    )
    (net (code "84") (name "Net-(U1-A0)") (class "Default")
      (node (ref "U1") (pin "14") (pinfunction "A0_14") (pintype "bidirectional"))
      (node (ref "U2") (pin "P3") (pinfunction "AD7_P3") (pintype "bidirectional"))
      (node (ref "U3") (pin "14") (pinfunction "A0_14") (pintype "bidirectional"))
    )
    (net (code "85") (name "Net-(U1-A1)") (class "Default")
      (node (ref "U1") (pin "13") (pinfunction "A1_13") (pintype "bidirectional"))
      (node (ref "U2") (pin "P4") (pinfunction "AD6_P4") (pintype "bidirectional"))
      (node (ref "U3") (pin "13") (pinfunction "A1_13") (pintype "bidirectional"))
    )
    (net (code "86") (name "Net-(U1-A2)") (class "Default")
      (node (ref "U1") (pin "12") (pinfunction "A2_12") (pintype "bidirectional"))
      (node (ref "U2") (pin "P5") (pinfunction "AD5_P5") (pintype "bidirectional"))
      (node (ref "U3") (pin "12") (pinfunction "A2_12") (pintype "bidirectional"))
    )
    (net (code "87") (name "Net-(U1-A3)") (class "Default")
      (node (ref "U1") (pin "11") (pinfunction "A3_11") (pintype "bidirectional"))
      (node (ref "U2") (pin "P6") (pinfunction "AD4_P6") (pintype "bidirectional"))
      (node (ref "U3") (pin "11") (pinfunction "A3_11") (pintype "bidirectional"))
    )
    (net (code "88") (name "Net-(U1-A4)") (class "Default")
      (node (ref "U1") (pin "8") (pinfunction "A4_8") (pintype "bidirectional"))
      (node (ref "U2") (pin "P7") (pinfunction "AD3_P7") (pintype "bidirectional"))
      (node (ref "U3") (pin "8") (pinfunction "A4_8") (pintype "bidirectional"))
    )
    (net (code "89") (name "Net-(U1-A5)") (class "Default")
      (node (ref "U1") (pin "7") (pinfunction "A5_7") (pintype "bidirectional"))
      (node (ref "U2") (pin "P8") (pinfunction "AD2_P8") (pintype "bidirectional"))
      (node (ref "U3") (pin "7") (pinfunction "A5_7") (pintype "bidirectional"))
    )
    (net (code "90") (name "Net-(U1-A6)") (class "Default")
      (node (ref "U1") (pin "6") (pinfunction "A6_6") (pintype "bidirectional"))
      (node (ref "U2") (pin "P9") (pinfunction "AD1_P9") (pintype "bidirectional"))
      (node (ref "U3") (pin "6") (pinfunction "A6_6") (pintype "bidirectional"))
    )
    (net (code "91") (name "Net-(U1-A7)") (class "Default")
      (node (ref "U1") (pin "10") (pinfunction "A7_10") (pintype "bidirectional"))
      (node (ref "U2") (pin "P10") (pinfunction "AD0_P10") (pintype "bidirectional"))
      (node (ref "U3") (pin "10") (pinfunction "A7_10") (pintype "bidirectional"))
    )
    (net (code "92") (name "Net-(U1-CAS*)") (class "Default")
      (node (ref "U1") (pin "16") (pinfunction "CAS*_16") (pintype "bidirectional"))
      (node (ref "U2") (pin "P2") (pinfunction "CAS*_P2") (pintype "bidirectional"))
      (node (ref "U3") (pin "16") (pinfunction "CAS*_16") (pintype "bidirectional"))
    )
    (net (code "93") (name "Net-(U1-DQ1)") (class "Default")
      (node (ref "U1") (pin "2") (pinfunction "DQ1_2") (pintype "bidirectional"))
      (node (ref "U2") (pin "P32") (pinfunction "RD0_P32") (pintype "bidirectional"))
    )
    (net (code "94") (name "Net-(U1-DQ2)") (class "Default")
      (node (ref "U1") (pin "3") (pinfunction "DQ2_3") (pintype "bidirectional"))
      (node (ref "U2") (pin "P31") (pinfunction "RD1_P31") (pintype "bidirectional"))
    )
    (net (code "95") (name "Net-(U1-DQ3)") (class "Default")
      (node (ref "U1") (pin "15") (pinfunction "DQ3_15") (pintype "bidirectional"))
      (node (ref "U2") (pin "P30") (pinfunction "RD2_P30") (pintype "bidirectional"))
    )
    (net (code "96") (name "Net-(U1-DQ4)") (class "Default")
      (node (ref "U1") (pin "17") (pinfunction "DQ4_17") (pintype "bidirectional"))
      (node (ref "U2") (pin "P29") (pinfunction "RD3_P29") (pintype "bidirectional"))
    )
    (net (code "97") (name "Net-(U1-RAS*)") (class "Default")
      (node (ref "U1") (pin "5") (pinfunction "RAS*_5") (pintype "bidirectional"))
      (node (ref "U2") (pin "P1") (pinfunction "RAS*_P1") (pintype "bidirectional"))
      (node (ref "U3") (pin "5") (pinfunction "RAS*_5") (pintype "bidirectional"))
    )
    (net (code "98") (name "Net-(U1-W*)") (class "Default")
      (node (ref "U1") (pin "4") (pinfunction "W*_4") (pintype "bidirectional"))
      (node (ref "U2") (pin "P11") (pinfunction "R/W*_P11") (pintype "bidirectional"))
      (node (ref "U3") (pin "4") (pinfunction "W*_4") (pintype "bidirectional"))
    )
    (net (code "99") (name "Net-(U2-COMVID)") (class "Default")
      (node (ref "Q2") (pin "B") (pinfunction "B_B") (pintype "passive"))
      (node (ref "R4") (pin "1") (pinfunction "1_1") (pintype "passive"))
      (node (ref "U2") (pin "P36") (pinfunction "COMVID_P36") (pintype "bidirectional"))
    )
    (net (code "100") (name "Net-(U2-RD4)") (class "Default")
      (node (ref "U2") (pin "P28") (pinfunction "RD4_P28") (pintype "bidirectional"))
      (node (ref "U3") (pin "2") (pinfunction "DQ1_2") (pintype "bidirectional"))
    )
    (net (code "101") (name "Net-(U2-RD5)") (class "Default")
      (node (ref "U2") (pin "P27") (pinfunction "RD5_P27") (pintype "bidirectional"))
      (node (ref "U3") (pin "3") (pinfunction "DQ2_3") (pintype "bidirectional"))
    )
    (net (code "102") (name "Net-(U2-RD6)") (class "Default")
      (node (ref "U2") (pin "P26") (pinfunction "RD6_P26") (pintype "bidirectional"))
      (node (ref "U3") (pin "15") (pinfunction "DQ3_15") (pintype "bidirectional"))
    )
    (net (code "103") (name "Net-(U2-RD7)") (class "Default")
      (node (ref "U2") (pin "P25") (pinfunction "RD7_P25") (pintype "bidirectional"))
      (node (ref "U3") (pin "17") (pinfunction "DQ4_17") (pintype "bidirectional"))
    )
    (net (code "104") (name "Net-(U2-XTAL1)") (class "Default")
      (node (ref "C8") (pin "2") (pinfunction "2_2") (pintype "passive"))
      (node (ref "Q1") (pin "1") (pinfunction "1_1") (pintype "passive"))
      (node (ref "U2") (pin "P40") (pinfunction "XTAL1_P40") (pintype "bidirectional"))
    )
    (net (code "105") (name "Net-(U2-XTAL2)") (class "Default")
      (node (ref "C9") (pin "2") (pinfunction "2_2") (pintype "passive"))
      (node (ref "Q1") (pin "2") (pinfunction "2_2") (pintype "passive"))
      (node (ref "U2") (pin "P39") (pinfunction "XTAL2_P39") (pintype "bidirectional"))
    )
    (net (code "106") (name "Net-(U4-SNDOUT)") (class "Default")
      (node (ref "C1") (pin "+") (pinfunction "+_+") (pintype "passive"))
      (node (ref "U4") (pin "P7") (pinfunction "SNDOUT_P7") (pintype "bidirectional"))
    )
    (net (code "107") (name "Net-(U11-SNDOUT)") (class "Default")
      (node (ref "C27") (pin "+") (pinfunction "+_+") (pintype "passive"))
      (node (ref "U11") (pin "P7") (pinfunction "SNDOUT_P7") (pintype "bidirectional"))
    )
    (net (code "108") (name "VCC") (class "Default")
      (node (ref "C11") (pin "+") (pinfunction "+_+") (pintype "passive"))
      (node (ref "C12") (pin "1") (pinfunction "1_1") (pintype "passive"))
      (node (ref "C13") (pin "1") (pinfunction "1_1") (pintype "passive"))
      (node (ref "C14") (pin "1") (pinfunction "1_1") (pintype "passive"))
      (node (ref "C15") (pin "1") (pinfunction "1_1") (pintype "passive"))
      (node (ref "C16") (pin "1") (pinfunction "1_1") (pintype "passive"))
      (node (ref "C17") (pin "1") (pinfunction "1_1") (pintype "passive"))
      (node (ref "C2") (pin "1") (pinfunction "1_1") (pintype "passive"))
      (node (ref "C20") (pin "1") (pinfunction "1_1") (pintype "passive"))
      (node (ref "C21") (pin "1") (pinfunction "1_1") (pintype "passive"))
      (node (ref "C22") (pin "1") (pinfunction "1_1") (pintype "passive"))
      (node (ref "C23") (pin "1") (pinfunction "1_1") (pintype "passive"))
      (node (ref "C24") (pin "1") (pinfunction "1_1") (pintype "passive"))
      (node (ref "C3") (pin "1") (pinfunction "1_1") (pintype "passive"))
      (node (ref "C4") (pin "1") (pinfunction "1_1") (pintype "passive"))
      (node (ref "C6") (pin "1") (pinfunction "1_1") (pintype "passive"))
      (node (ref "IC1") (pin "14") (pinfunction "VCC_14") (pintype "power_in"))
      (node (ref "IC10") (pin "20") (pinfunction "VCC_20") (pintype "power_in"))
      (node (ref "IC2") (pin "14") (pinfunction "VCC_14") (pintype "power_in"))
      (node (ref "IC3") (pin "14") (pinfunction "VCC_14") (pintype "power_in"))
      (node (ref "IC4") (pin "14") (pinfunction "VCC_14") (pintype "power_in"))
      (node (ref "IC5") (pin "14") (pinfunction "VCC_14") (pintype "power_in"))
      (node (ref "IC7") (pin "14") (pinfunction "VCC_14") (pintype "power_in"))
      (node (ref "IC9") (pin "14") (pinfunction "VCC_14") (pintype "power_in"))
      (node (ref "Q2") (pin "C") (pinfunction "C_C") (pintype "passive"))
      (node (ref "R10") (pin "1") (pinfunction "1_1") (pintype "passive"))
      (node (ref "R11") (pin "1") (pinfunction "1_1") (pintype "passive"))
      (node (ref "R2") (pin "1") (pinfunction "1_1") (pintype "passive"))
      (node (ref "R7") (pin "1") (pinfunction "1_1") (pintype "passive"))
      (node (ref "R8") (pin "1") (pinfunction "1_1") (pintype "passive"))
      (node (ref "R9") (pin "1") (pinfunction "1_1") (pintype "passive"))
      (node (ref "REG2") (pin "P$3") (pinfunction "VOUT_P$3") (pintype "bidirectional"))
      (node (ref "SW1") (pin "P$15") (pinfunction "P$15_P$15") (pintype "bidirectional"))
      (node (ref "SW3") (pin "P$15") (pinfunction "P$15_P$15") (pintype "bidirectional"))
      (node (ref "U1") (pin "9") (pinfunction "VDD_9") (pintype "bidirectional"))
      (node (ref "U11") (pin "P16") (pinfunction "VCC_P16") (pintype "bidirectional"))
      (node (ref "U2") (pin "P33") (pinfunction "VDD_P33") (pintype "bidirectional"))
      (node (ref "U3") (pin "9") (pinfunction "VDD_9") (pintype "bidirectional"))
      (node (ref "U4") (pin "P16") (pinfunction "VCC_P16") (pintype "bidirectional"))
    )
    (net (code "109") (name "unconnected-(IC1A-O-Pad2)") (class "Default")
      (node (ref "IC1") (pin "2") (pinfunction "O_2") (pintype "output"))
    )
    (net (code "110") (name "unconnected-(IC7B-O-Pad10)") (class "Default")
      (node (ref "IC7") (pin "10") (pinfunction "O_10") (pintype "output"))
    )
    (net (code "111") (name "unconnected-(IC7C-O-Pad8)") (class "Default")
      (node (ref "IC7") (pin "8") (pinfunction "O_8") (pintype "output"))
    )
    (net (code "112") (name "unconnected-(IC7D-O-Pad2)") (class "Default")
      (node (ref "IC7") (pin "2") (pinfunction "O_2") (pintype "output"))
    )
    (net (code "113") (name "unconnected-(IC7E-O-Pad4)") (class "Default")
      (node (ref "IC7") (pin "4") (pinfunction "O_4") (pintype "output"))
    )
    (net (code "114") (name "unconnected-(IC7F-O-Pad6)") (class "Default")
      (node (ref "IC7") (pin "6") (pinfunction "O_6") (pintype "output"))
    )
    (net (code "115") (name "unconnected-(IC9C-O-Pad8)") (class "Default")
      (node (ref "IC9") (pin "8") (pinfunction "O_8") (pintype "output"))
    )
    (net (code "116") (name "unconnected-(IC9D-O-Pad11)") (class "Default")
      (node (ref "IC9") (pin "11") (pinfunction "O_11") (pintype "output"))
    )
    (net (code "117") (name "unconnected-(JOYSTICK-Pad5)") (class "Default")
      (node (ref "JOYSTICK") (pin "5") (pinfunction "5_5") (pintype "passive"))
    )
    (net (code "118") (name "unconnected-(JOYSTICK-Pad7)") (class "Default")
      (node (ref "JOYSTICK") (pin "7") (pinfunction "7_7") (pintype "passive"))
    )
    (net (code "119") (name "unconnected-(JOYSTICK-Pad9)") (class "Default")
      (node (ref "JOYSTICK") (pin "9") (pinfunction "9_9") (pintype "passive"))
    )
    (net (code "120") (name "unconnected-(U$1-A8-PadP$11)") (class "Default")
      (node (ref "U$1") (pin "P$11") (pinfunction "A8_P$11") (pintype "bidirectional"))
    )
    (net (code "121") (name "unconnected-(U$1-A9-PadP$17)") (class "Default")
      (node (ref "U$1") (pin "P$17") (pinfunction "A9_P$17") (pintype "bidirectional"))
    )
    (net (code "122") (name "unconnected-(U$1-A10-PadP$4)") (class "Default")
      (node (ref "U$1") (pin "P$4") (pinfunction "A10_P$4") (pintype "bidirectional"))
    )
    (net (code "123") (name "unconnected-(U$1-A11-PadP$9)") (class "Default")
      (node (ref "U$1") (pin "P$9") (pinfunction "A11_P$9") (pintype "bidirectional"))
    )
    (net (code "124") (name "unconnected-(U$1-A12-PadP$5)") (class "Default")
      (node (ref "U$1") (pin "P$5") (pinfunction "A12_P$5") (pintype "bidirectional"))
    )
    (net (code "125") (name "unconnected-(U$1-A13-PadP$6)") (class "Default")
      (node (ref "U$1") (pin "P$6") (pinfunction "A13_P$6") (pintype "bidirectional"))
    )
    (net (code "126") (name "unconnected-(U$1-A14-PadP$10)") (class "Default")
      (node (ref "U$1") (pin "P$10") (pinfunction "A14_P$10") (pintype "bidirectional"))
    )
    (net (code "127") (name "unconnected-(U$1-A15-PadP$7)") (class "Default")
      (node (ref "U$1") (pin "P$7") (pinfunction "A15_P$7") (pintype "bidirectional"))
    )
    (net (code "128") (name "unconnected-(U$1-CAS*-PadP$3)") (class "Default")
      (node (ref "U$1") (pin "P$3") (pinfunction "CAS*_P$3") (pintype "bidirectional"))
    )
    (net (code "129") (name "unconnected-(U$1-INT*-PadP$21)") (class "Default")
      (node (ref "U$1") (pin "P$21") (pinfunction "INT*_P$21") (pintype "bidirectional"))
    )
    (net (code "130") (name "unconnected-(U$1-INTAK*-PadP$14)") (class "Default")
      (node (ref "U$1") (pin "P$14") (pinfunction "INTAK*_P$14") (pintype "bidirectional"))
    )
    (net (code "131") (name "unconnected-(U$1-MUX-PadP$16)") (class "Default")
      (node (ref "U$1") (pin "P$16") (pinfunction "MUX_P$16") (pintype "bidirectional"))
    )
    (net (code "132") (name "unconnected-(U$1-NC-PadP$39)") (class "Default")
      (node (ref "U$1") (pin "P$39") (pinfunction "NC_P$39") (pintype "bidirectional"))
    )
    (net (code "133") (name "unconnected-(U$1-RAS*-PadP$1)") (class "Default")
      (node (ref "U$1") (pin "P$1") (pinfunction "RAS*_P$1") (pintype "bidirectional"))
    )
    (net (code "134") (name "unconnected-(U$1-RD*-PadP$15)") (class "Default")
      (node (ref "U$1") (pin "P$15") (pinfunction "RD*_P$15") (pintype "bidirectional"))
    )
    (net (code "135") (name "unconnected-(U$1-TEST*-PadP$23)") (class "Default")
      (node (ref "U$1") (pin "P$23") (pinfunction "TEST*_P$23") (pintype "bidirectional"))
    )
    (net (code "136") (name "unconnected-(U$1-WAIT*-PadP$33)") (class "Default")
      (node (ref "U$1") (pin "P$33") (pinfunction "WAIT*_P$33") (pintype "bidirectional"))
    )
    (net (code "137") (name "unconnected-(U$1-WR*-PadP$13)") (class "Default")
      (node (ref "U$1") (pin "P$13") (pinfunction "WR*_P$13") (pintype "bidirectional"))
    )
    (net (code "138") (name "unconnected-(U2-CPUCLK-PadP38)") (class "Default")
      (node (ref "U2") (pin "P38") (pinfunction "CPUCLK_P38") (pintype "bidirectional"))
    )
    (net (code "139") (name "unconnected-(U2-EXTVDP-PadP35)") (class "Default")
      (node (ref "U2") (pin "P35") (pinfunction "EXTVDP_P35") (pintype "bidirectional"))
    )
    (net (code "140") (name "unconnected-(U2-INT*-PadP16)") (class "Default")
      (node (ref "U2") (pin "P16") (pinfunction "INT*_P16") (pintype "bidirectional"))
    )
    (net (code "141") (name "unconnected-(U2-NC-PadP37)") (class "Default")
      (node (ref "U2") (pin "P37") (pinfunction "NC_P37") (pintype "bidirectional"))
    )
    (net (code "142") (name "unconnected-(U4-NC-PadP9)") (class "Default")
      (node (ref "U4") (pin "P9") (pinfunction "NC_P9") (pintype "bidirectional"))
    )
    (net (code "143") (name "unconnected-(U4-READY-PadP4)") (class "Default")
      (node (ref "U4") (pin "P4") (pinfunction "READY_P4") (pintype "bidirectional"))
    )
    (net (code "144") (name "unconnected-(U11-NC-PadP9)") (class "Default")
      (node (ref "U11") (pin "P9") (pinfunction "NC_P9") (pintype "bidirectional"))
    )
    (net (code "145") (name "unconnected-(U11-READY-PadP4)") (class "Default")
      (node (ref "U11") (pin "P4") (pinfunction "READY_P4") (pintype "bidirectional"))
    )
  )
)
